# schematics.net
KiCad netlist of a schematic drawn in EAGLE
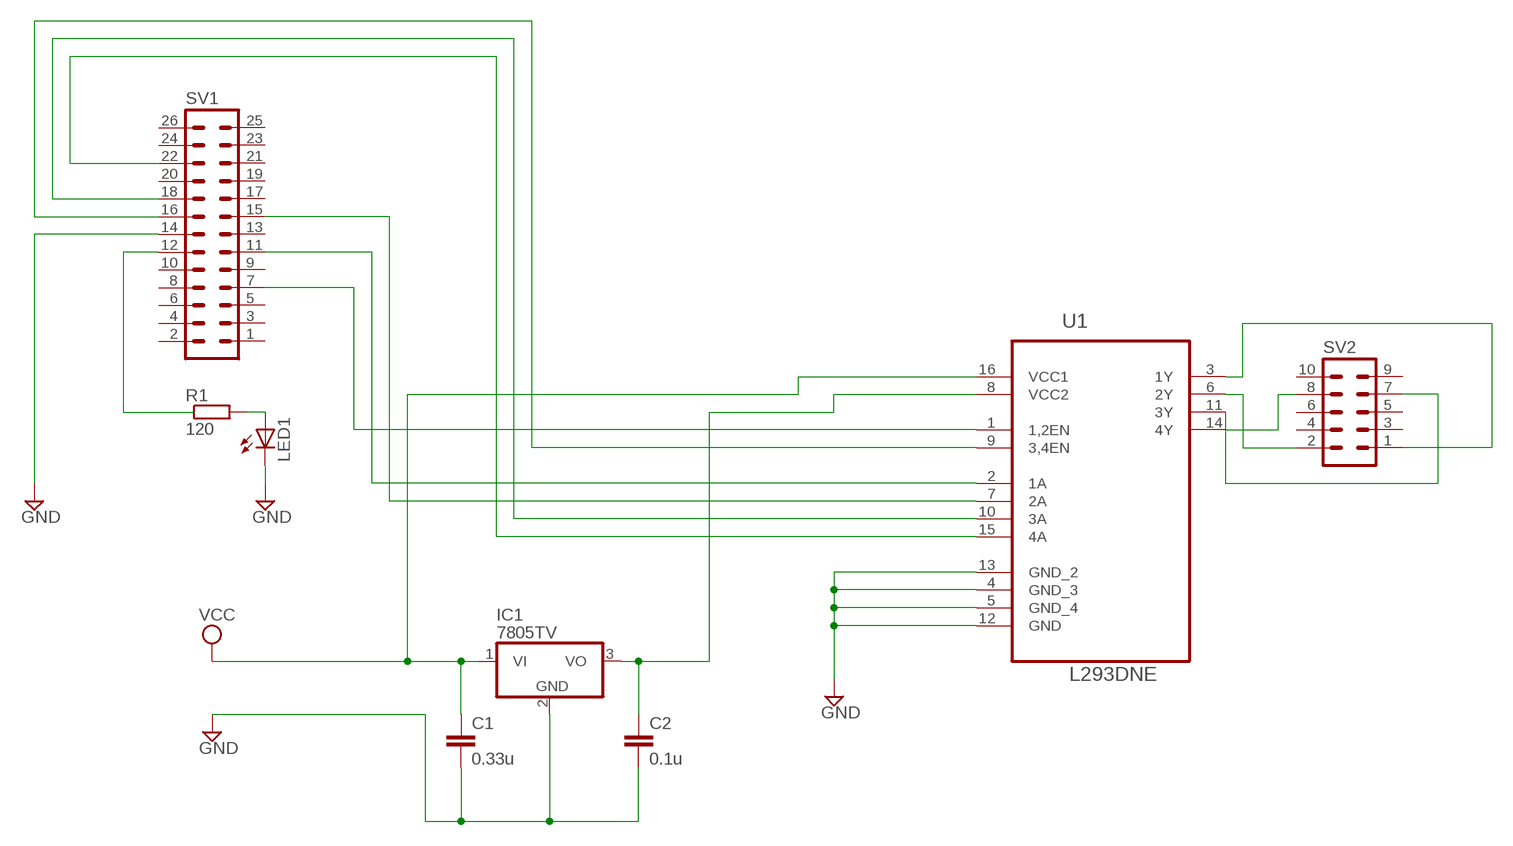
[diagram p0: schematic, sheet 1]

(export (version "E")
  (design (tool "Eeschema 10.0.6"))
  (components
    (comp (ref "C1")
      (value "0.33u")
      (footprint "eagle-import:C025-025X050")
      (libsource (lib "eagle-import") (part "C-EU025-025X050"))
    )
    (comp (ref "C2")
      (value "0.1u")
      (footprint "eagle-import:C025-025X050")
      (libsource (lib "eagle-import") (part "C-EU025-025X050"))
    )
    (comp (ref "IC1")
      (value "7805TV")
      (footprint "eagle-import:TO220V")
      (libsource (lib "eagle-import") (part "78TV05"))
    )
    (comp (ref "LED1")
      (value "LED5MM")
      (footprint "eagle-import:LED5MM")
      (libsource (lib "eagle-import") (part "LED5MM"))
    )
    (comp (ref "R1")
      (value "120")
      (footprint "eagle-import:0207_10")
      (libsource (lib "eagle-import") (part "R-EU_0207/10"))
    )
    (comp (ref "SV1")
      (value "MA13-2")
      (footprint "eagle-import:MA13-2")
      (libsource (lib "eagle-import") (part "MA13-2"))
    )
    (comp (ref "SV2")
      (value "MA05-2")
      (footprint "eagle-import:MA05-2")
      (libsource (lib "eagle-import") (part "MA05-2"))
    )
    (comp (ref "U1")
      (value "L293DNE")
      (footprint "eagle-import:DIP254P762X508-16")
      (libsource (lib "eagle-import") (part "L293DNE"))
    )
  )
  (nets
    (net (code "1") (name "GND") (class "Default")
      (node (ref "C1") (pin "2") (pinfunction "2_2") (pintype "passive"))
      (node (ref "C2") (pin "2") (pinfunction "2_2") (pintype "passive"))
      (node (ref "IC1") (pin "2") (pinfunction "GND_2") (pintype "passive"))
      (node (ref "LED1") (pin "K") (pinfunction "C_K") (pintype "passive"))
      (node (ref "SV1") (pin "14") (pinfunction "14_14") (pintype "passive"))
      (node (ref "U1") (pin "12") (pinfunction "GND_12") (pintype "passive"))
      (node (ref "U1") (pin "13") (pinfunction "GND_2_13") (pintype "passive"))
      (node (ref "U1") (pin "4") (pinfunction "GND_3_4") (pintype "passive"))
      (node (ref "U1") (pin "5") (pinfunction "GND_4_5") (pintype "passive"))
    )
    (net (code "2") (name "Net-(IC1-VO)") (class "Default")
      (node (ref "C2") (pin "1") (pinfunction "1_1") (pintype "passive"))
      (node (ref "IC1") (pin "3") (pinfunction "VO_3") (pintype "passive"))
      (node (ref "U1") (pin "8") (pinfunction "VCC2_8") (pintype "power_in"))
    )
    (net (code "3") (name "Net-(LED1-PadA)") (class "Default")
      (node (ref "LED1") (pin "A") (pinfunction "A_A") (pintype "passive"))
      (node (ref "R1") (pin "2") (pinfunction "2_2") (pintype "passive"))
    )
    (net (code "4") (name "Net-(R1-Pad1)") (class "Default")
      (node (ref "R1") (pin "1") (pinfunction "1_1") (pintype "passive"))
      (node (ref "SV1") (pin "12") (pinfunction "12_12") (pintype "passive"))
    )
    (net (code "5") (name "Net-(U1-1,2EN)") (class "Default")
      (node (ref "SV1") (pin "7") (pinfunction "7_7") (pintype "passive"))
      (node (ref "U1") (pin "1") (pinfunction "1,2EN_1") (pintype "input"))
    )
    (net (code "6") (name "Net-(U1-1A)") (class "Default")
      (node (ref "SV1") (pin "11") (pinfunction "11_11") (pintype "passive"))
      (node (ref "U1") (pin "2") (pinfunction "1A_2") (pintype "input"))
    )
    (net (code "7") (name "Net-(U1-1Y)") (class "Default")
      (node (ref "SV2") (pin "1") (pinfunction "1_1") (pintype "passive"))
      (node (ref "U1") (pin "3") (pinfunction "1Y_3") (pintype "output"))
    )
    (net (code "8") (name "Net-(U1-2A)") (class "Default")
      (node (ref "SV1") (pin "15") (pinfunction "15_15") (pintype "passive"))
      (node (ref "U1") (pin "7") (pinfunction "2A_7") (pintype "input"))
    )
    (net (code "9") (name "Net-(U1-2Y)") (class "Default")
      (node (ref "SV2") (pin "2") (pinfunction "2_2") (pintype "passive"))
      (node (ref "U1") (pin "6") (pinfunction "2Y_6") (pintype "output"))
    )
    (net (code "10") (name "Net-(U1-3,4EN)") (class "Default")
      (node (ref "SV1") (pin "16") (pinfunction "16_16") (pintype "passive"))
      (node (ref "U1") (pin "9") (pinfunction "3,4EN_9") (pintype "input"))
    )
    (net (code "11") (name "Net-(U1-3A)") (class "Default")
      (node (ref "SV1") (pin "18") (pinfunction "18_18") (pintype "passive"))
      (node (ref "U1") (pin "10") (pinfunction "3A_10") (pintype "input"))
    )
    (net (code "12") (name "Net-(U1-3Y)") (class "Default")
      (node (ref "SV2") (pin "7") (pinfunction "7_7") (pintype "passive"))
      (node (ref "U1") (pin "11") (pinfunction "3Y_11") (pintype "output"))
    )
    (net (code "13") (name "Net-(U1-4A)") (class "Default")
      (node (ref "SV1") (pin "22") (pinfunction "22_22") (pintype "passive"))
      (node (ref "U1") (pin "15") (pinfunction "4A_15") (pintype "input"))
    )
    (net (code "14") (name "Net-(U1-4Y)") (class "Default")
      (node (ref "SV2") (pin "8") (pinfunction "8_8") (pintype "passive"))
      (node (ref "U1") (pin "14") (pinfunction "4Y_14") (pintype "output"))
    )
    (net (code "15") (name "VCC") (class "Default")
      (node (ref "C1") (pin "1") (pinfunction "1_1") (pintype "passive"))
      (node (ref "IC1") (pin "1") (pinfunction "VI_1") (pintype "input"))
      (node (ref "U1") (pin "16") (pinfunction "VCC1_16") (pintype "power_in"))
    )
    (net (code "16") (name "unconnected-(SV1-Pad1)") (class "Default")
      (node (ref "SV1") (pin "1") (pinfunction "1_1") (pintype "passive"))
    )
    (net (code "17") (name "unconnected-(SV1-Pad2)") (class "Default")
      (node (ref "SV1") (pin "2") (pinfunction "2_2") (pintype "passive"))
    )
    (net (code "18") (name "unconnected-(SV1-Pad3)") (class "Default")
      (node (ref "SV1") (pin "3") (pinfunction "3_3") (pintype "passive"))
    )
    (net (code "19") (name "unconnected-(SV1-Pad4)") (class "Default")
      (node (ref "SV1") (pin "4") (pinfunction "4_4") (pintype "passive"))
    )
    (net (code "20") (name "unconnected-(SV1-Pad5)") (class "Default")
      (node (ref "SV1") (pin "5") (pinfunction "5_5") (pintype "passive"))
    )
    (net (code "21") (name "unconnected-(SV1-Pad6)") (class "Default")
      (node (ref "SV1") (pin "6") (pinfunction "6_6") (pintype "passive"))
    )
    (net (code "22") (name "unconnected-(SV1-Pad8)") (class "Default")
      (node (ref "SV1") (pin "8") (pinfunction "8_8") (pintype "passive"))
    )
    (net (code "23") (name "unconnected-(SV1-Pad9)") (class "Default")
      (node (ref "SV1") (pin "9") (pinfunction "9_9") (pintype "passive"))
    )
    (net (code "24") (name "unconnected-(SV1-Pad10)") (class "Default")
      (node (ref "SV1") (pin "10") (pinfunction "10_10") (pintype "passive"))
    )
    (net (code "25") (name "unconnected-(SV1-Pad13)") (class "Default")
      (node (ref "SV1") (pin "13") (pinfunction "13_13") (pintype "passive"))
    )
    (net (code "26") (name "unconnected-(SV1-Pad17)") (class "Default")
      (node (ref "SV1") (pin "17") (pinfunction "17_17") (pintype "passive"))
    )
    (net (code "27") (name "unconnected-(SV1-Pad19)") (class "Default")
      (node (ref "SV1") (pin "19") (pinfunction "19_19") (pintype "passive"))
    )
    (net (code "28") (name "unconnected-(SV1-Pad20)") (class "Default")
      (node (ref "SV1") (pin "20") (pinfunction "20_20") (pintype "passive"))
    )
    (net (code "29") (name "unconnected-(SV1-Pad21)") (class "Default")
      (node (ref "SV1") (pin "21") (pinfunction "21_21") (pintype "passive"))
    )
    (net (code "30") (name "unconnected-(SV1-Pad23)") (class "Default")
      (node (ref "SV1") (pin "23") (pinfunction "23_23") (pintype "passive"))
    )
    (net (code "31") (name "unconnected-(SV1-Pad24)") (class "Default")
      (node (ref "SV1") (pin "24") (pinfunction "24_24") (pintype "passive"))
    )
    (net (code "32") (name "unconnected-(SV1-Pad25)") (class "Default")
      (node (ref "SV1") (pin "25") (pinfunction "25_25") (pintype "passive"))
    )
    (net (code "33") (name "unconnected-(SV1-Pad26)") (class "Default")
      (node (ref "SV1") (pin "26") (pinfunction "26_26") (pintype "passive"))
    )
    (net (code "34") (name "unconnected-(SV2-Pad3)") (class "Default")
      (node (ref "SV2") (pin "3") (pinfunction "3_3") (pintype "passive"))
    )
    (net (code "35") (name "unconnected-(SV2-Pad4)") (class "Default")
      (node (ref "SV2") (pin "4") (pinfunction "4_4") (pintype "passive"))
    )
    (net (code "36") (name "unconnected-(SV2-Pad5)") (class "Default")
      (node (ref "SV2") (pin "5") (pinfunction "5_5") (pintype "passive"))
    )
    (net (code "37") (name "unconnected-(SV2-Pad6)") (class "Default")
      (node (ref "SV2") (pin "6") (pinfunction "6_6") (pintype "passive"))
    )
    (net (code "38") (name "unconnected-(SV2-Pad9)") (class "Default")
      (node (ref "SV2") (pin "9") (pinfunction "9_9") (pintype "passive"))
    )
    (net (code "39") (name "unconnected-(SV2-Pad10)") (class "Default")
      (node (ref "SV2") (pin "10") (pinfunction "10_10") (pintype "passive"))
    )
  )
)
